# Napajanje.net
KiCad netlist of a schematic drawn in Altium Designer
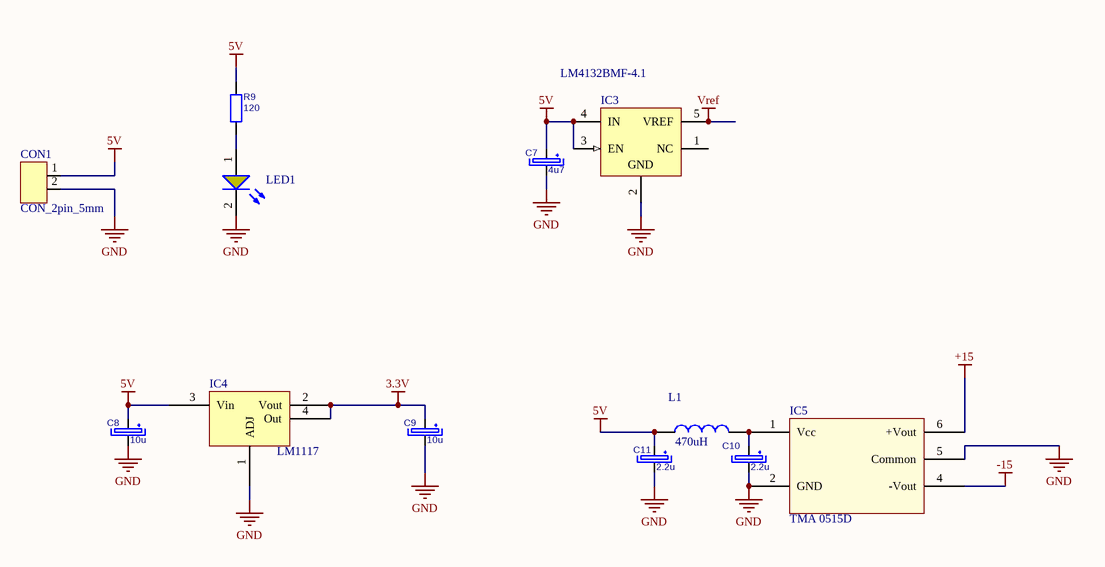
[diagram p0: Napajanje.SchDoc]

(export (version "E")
  (design (tool "Eeschema 10.0.6"))
  (components
    (comp (ref "C7")
      (value "4u7")
      (footprint "C Tantal A")
      (description "Capacitor Polarized")
      (libsource (lib "Vremenska") (part "C+"))
    )
    (comp (ref "C8")
      (value "10u")
      (footprint "C Tantal B")
      (description "Capacitor Polarized")
      (libsource (lib "Vremenska") (part "C+"))
    )
    (comp (ref "C9")
      (value "10u")
      (footprint "C Tantal B")
      (description "Capacitor Polarized")
      (libsource (lib "Vremenska") (part "C+"))
    )
    (comp (ref "C10")
      (value "2.2u")
      (footprint "C Tantal B")
      (description "Capacitor Polarized")
      (libsource (lib "Vremenska") (part "C+"))
    )
    (comp (ref "C11")
      (value "2.2u")
      (footprint "C Tantal B")
      (description "Capacitor Polarized")
      (libsource (lib "Vremenska") (part "C+"))
    )
    (comp (ref "CON1")
      (value "CON_2pin_5mm")
      (footprint "CON_2pin_5mm")
      (description "Konektor za  Bernic ohišja Serija 605, 5 mm raster")
      (libsource (lib "Vremenska") (part "CON_2pin_5mm"))
    )
    (comp (ref "IC3")
      (value "LM4132BMF-4.1")
      (footprint "SOT95P280X145-5N")
      (description "Precision Low Dropout Voltage Reference, 5-pin SOT-23")
      (fields (field (name "MANUFACTURER") "National Semiconductor"))
      (libsource (lib "National Semiconductor Voltage Reference") (part "LM4132BMF-4.1"))
    )
    (comp (ref "IC4")
      (value "LM1117")
      (footprint "SOT230P700X180-4N")
      (libsource (lib "2016-11-04_16-51-30") (part "LM1117"))
    )
    (comp (ref "IC5")
      (value "TMA 0515D")
      (footprint "TMA 0515D")
      (libsource (lib "2016-11-04_16-51-30") (part "TMA 0515D"))
    )
    (comp (ref "L1")
      (value "470uH")
      (footprint "WE-PD2_7850")
      (description "WE-PD2 SMD Power Inductor, size 7850, 1000uH")
      (fields (field (name "Comment") "WE-PD2, 74477530"))
      (libsource (lib "ALTIUM-WE-PD2-rev16a") (part "WE-PD2, 74477530"))
    )
    (comp (ref "LED1")
      (value "150060YS75000")
      (footprint "LED_0603_Yellow")
      (description "SMD mono-color Chip LED, WL-SMCW, Yellow")
      (fields
        (field (name "MANUFACTURER") "W黵th Elektronik eiSos GmbH")
        (field (name "CREATED BY") "Christin Otto")
      )
      (libsource (lib "WL-SMCW_rev15b") (part "WL-SMCW 0603  150060YS75000"))
    )
    (comp (ref "R9")
      (value "120")
      (footprint "R0805")
      (description "R")
      (libsource (lib "General") (part "R"))
    )
  )
  (nets
    (net (code "1") (name "+15") (class "Default")
      (node (ref "IC5") (pin "6") (pinfunction "+Vout_6") (pintype "passive"))
    )
    (net (code "2") (name "-15") (class "Default")
      (node (ref "IC5") (pin "4") (pinfunction "-Vout_4") (pintype "passive"))
    )
    (net (code "3") (name "3.3V") (class "Default")
      (node (ref "C9") (pin "1") (pinfunction "1_1") (pintype "passive"))
      (node (ref "IC4") (pin "2") (pinfunction "Vout_2") (pintype "passive"))
      (node (ref "IC4") (pin "4") (pinfunction "Out_4") (pintype "passive"))
    )
    (net (code "4") (name "5V") (class "Default")
      (node (ref "C11") (pin "1") (pinfunction "1_1") (pintype "passive"))
      (node (ref "C7") (pin "1") (pinfunction "1_1") (pintype "passive"))
      (node (ref "C8") (pin "1") (pinfunction "1_1") (pintype "passive"))
      (node (ref "CON1") (pin "1") (pinfunction "1_1") (pintype "passive"))
      (node (ref "IC3") (pin "3") (pinfunction "EN_3") (pintype "input"))
      (node (ref "IC3") (pin "4") (pinfunction "IN_4") (pintype "power_in"))
      (node (ref "IC4") (pin "3") (pinfunction "Vin_3") (pintype "passive"))
      (node (ref "L1") (pin "1") (pinfunction "1_1") (pintype "passive"))
      (node (ref "R9") (pin "1") (pintype "passive"))
    )
    (net (code "5") (name "GND") (class "Default")
      (node (ref "C10") (pin "2") (pinfunction "2_2") (pintype "passive"))
      (node (ref "C11") (pin "2") (pinfunction "2_2") (pintype "passive"))
      (node (ref "C7") (pin "2") (pinfunction "2_2") (pintype "passive"))
      (node (ref "C8") (pin "2") (pinfunction "2_2") (pintype "passive"))
      (node (ref "C9") (pin "2") (pinfunction "2_2") (pintype "passive"))
      (node (ref "CON1") (pin "2") (pinfunction "2_2") (pintype "passive"))
      (node (ref "IC3") (pin "2") (pinfunction "GND_2") (pintype "power_in"))
      (node (ref "IC4") (pin "1") (pinfunction "ADJ_1") (pintype "passive"))
      (node (ref "IC5") (pin "2") (pinfunction "GND_2") (pintype "passive"))
      (node (ref "IC5") (pin "5") (pinfunction "Common_5") (pintype "passive"))
      (node (ref "LED1") (pin "2") (pinfunction "C_2") (pintype "passive"))
    )
    (net (code "6") (name "Net-(IC5-Vcc)") (class "Default")
      (node (ref "C10") (pin "1") (pinfunction "1_1") (pintype "passive"))
      (node (ref "IC5") (pin "1") (pinfunction "Vcc_1") (pintype "passive"))
      (node (ref "L1") (pin "2") (pinfunction "2_2") (pintype "passive"))
    )
    (net (code "7") (name "Net-(LED1-A)") (class "Default")
      (node (ref "LED1") (pin "1") (pinfunction "A_1") (pintype "passive"))
      (node (ref "R9") (pin "2") (pintype "passive"))
    )
    (net (code "8") (name "Vref") (class "Default")
      (node (ref "IC3") (pin "5") (pinfunction "VREF_5") (pintype "power_in"))
    )
    (net (code "9") (name "unconnected-(IC3-NC-Pad1)") (class "Default")
      (node (ref "IC3") (pin "1") (pinfunction "NC_1") (pintype "passive"))
    )
  )
)
